# Terminierung_RS485-007.net
KiCad netlist of a schematic drawn in EAGLE
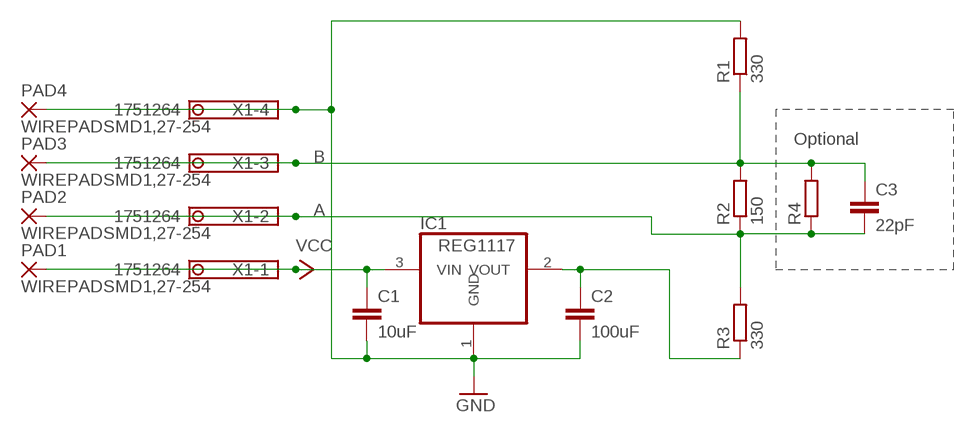
[diagram p0: schematic, sheet 1]

(export (version "E")
  (design (tool "Eeschema 10.0.6"))
  (components
    (comp (ref "C1")
      (value "10uF")
      (footprint "eagle-import:C0805K")
      (libsource (lib "eagle-import") (part "C-EUC0805K"))
    )
    (comp (ref "C2")
      (value "100uF")
      (footprint "eagle-import:C0805K")
      (libsource (lib "eagle-import") (part "C-EUC0805K"))
    )
    (comp (ref "C3")
      (value "22pF")
      (footprint "eagle-import:C0805K")
      (libsource (lib "eagle-import") (part "C-EUC0805K"))
    )
    (comp (ref "IC1")
      (value "REG1117")
      (footprint "eagle-import:SOT223")
      (libsource (lib "eagle-import") (part "REG1117"))
    )
    (comp (ref "PAD1")
      (value "WIREPADSMD1,27-254")
      (footprint "eagle-import:SMD1,27-2,54")
      (libsource (lib "eagle-import") (part "WIREPADSMD1,27-254"))
    )
    (comp (ref "PAD2")
      (value "WIREPADSMD1,27-254")
      (footprint "eagle-import:SMD1,27-2,54")
      (libsource (lib "eagle-import") (part "WIREPADSMD1,27-254"))
    )
    (comp (ref "PAD3")
      (value "WIREPADSMD1,27-254")
      (footprint "eagle-import:SMD1,27-2,54")
      (libsource (lib "eagle-import") (part "WIREPADSMD1,27-254"))
    )
    (comp (ref "PAD4")
      (value "WIREPADSMD1,27-254")
      (footprint "eagle-import:SMD1,27-2,54")
      (libsource (lib "eagle-import") (part "WIREPADSMD1,27-254"))
    )
    (comp (ref "R1")
      (value "330")
      (footprint "eagle-import:R0805")
      (libsource (lib "eagle-import") (part "R-EU_R0805"))
    )
    (comp (ref "R2")
      (value "150")
      (footprint "eagle-import:R0805")
      (libsource (lib "eagle-import") (part "R-EU_R0805"))
    )
    (comp (ref "R3")
      (value "330")
      (footprint "eagle-import:R0805")
      (libsource (lib "eagle-import") (part "R-EU_R0805"))
    )
    (comp (ref "R4")
      (value "R-EU_M1206")
      (footprint "eagle-import:M1206")
      (libsource (lib "eagle-import") (part "R-EU_M1206"))
    )
    (comp (ref "X1")
      (value "1751264")
      (footprint "eagle-import:1751264")
      (fields (field (name "MF") "VIN"))
      (libsource (lib "eagle-import") (part "1751264"))
    )
  )
  (nets
    (net (code "1") (name "/A") (class "Default")
      (node (ref "C3") (pin "2") (pinfunction "2_2") (pintype "passive"))
      (node (ref "PAD2") (pin "1") (pinfunction "P_1") (pintype "passive"))
      (node (ref "R2") (pin "1") (pinfunction "1_1") (pintype "passive"))
      (node (ref "R3") (pin "2") (pinfunction "2_2") (pintype "passive"))
      (node (ref "R4") (pin "1") (pinfunction "1_1") (pintype "passive"))
      (node (ref "X1") (pin "2") (pinfunction "K_2") (pintype "passive"))
    )
    (net (code "2") (name "/B") (class "Default")
      (node (ref "C3") (pin "1") (pinfunction "1_1") (pintype "passive"))
      (node (ref "PAD3") (pin "1") (pinfunction "P_1") (pintype "passive"))
      (node (ref "R1") (pin "1") (pinfunction "1_1") (pintype "passive"))
      (node (ref "R2") (pin "2") (pinfunction "2_2") (pintype "passive"))
      (node (ref "R4") (pin "2") (pinfunction "2_2") (pintype "passive"))
      (node (ref "X1") (pin "3") (pinfunction "K_3") (pintype "passive"))
    )
    (net (code "3") (name "GND") (class "Default")
      (node (ref "C1") (pin "2") (pinfunction "2_2") (pintype "passive"))
      (node (ref "C2") (pin "2") (pinfunction "2_2") (pintype "passive"))
      (node (ref "IC1") (pin "1") (pinfunction "GND_1") (pintype "power_in"))
      (node (ref "PAD4") (pin "1") (pinfunction "P_1") (pintype "passive"))
      (node (ref "R1") (pin "2") (pinfunction "2_2") (pintype "passive"))
      (node (ref "X1") (pin "4") (pinfunction "K_4") (pintype "passive"))
    )
    (net (code "4") (name "Net-(IC1-VOUT)") (class "Default")
      (node (ref "C2") (pin "1") (pinfunction "1_1") (pintype "passive"))
      (node (ref "IC1") (pin "2") (pinfunction "VOUT_2") (pintype "output"))
      (node (ref "R3") (pin "1") (pinfunction "1_1") (pintype "passive"))
    )
    (net (code "5") (name "VCC") (class "Default")
      (node (ref "C1") (pin "1") (pinfunction "1_1") (pintype "passive"))
      (node (ref "IC1") (pin "3") (pinfunction "VIN_3") (pintype "input"))
      (node (ref "PAD1") (pin "1") (pinfunction "P_1") (pintype "passive"))
      (node (ref "X1") (pin "1") (pinfunction "K_1") (pintype "passive"))
    )
  )
)
